# LED-Gauge-Panel.net
KiCad netlist of a schematic drawn in EAGLE
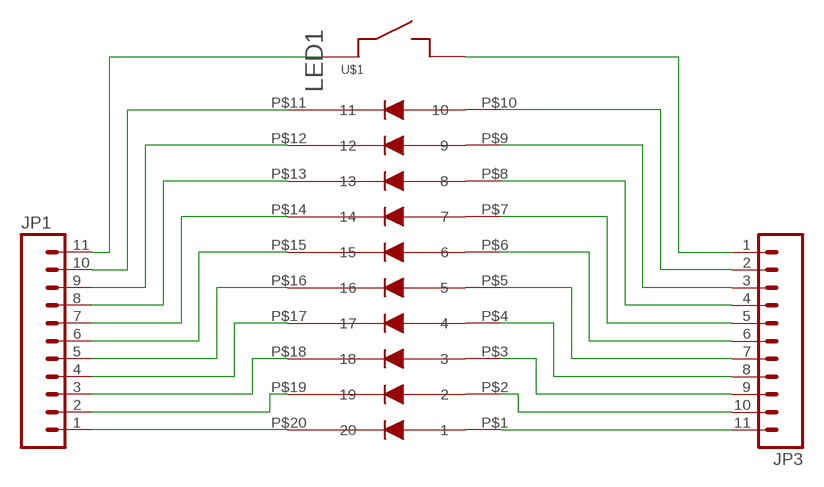
[diagram p0: schematic, sheet 1]

(export (version "E")
  (design (tool "Eeschema 10.0.6"))
  (components
    (comp (ref "JP1")
      (value "M11PTH")
      (footprint "eagle-import:1X11")
      (libsource (lib "eagle-import") (part "M11PTH"))
    )
    (comp (ref "JP3")
      (value "M11PTH")
      (footprint "eagle-import:1X11")
      (libsource (lib "eagle-import") (part "M11PTH"))
    )
    (comp (ref "LED1")
      (value "LED-DC7G3HWA")
      (footprint "eagle-import:LED-10")
      (libsource (lib "eagle-import") (part "LED-DC7G3HWA"))
    )
    (comp (ref "U$1")
      (value "MOMENTARY-SWITCH-EVQ1")
      (footprint "eagle-import:EVQ11")
      (libsource (lib "eagle-import") (part "MOMENTARY-SWITCH-EVQ1"))
    )
  )
  (nets
    (net (code "1") (name "Net-(JP1-Pad11)") (class "Default")
      (node (ref "JP1") (pin "11") (pinfunction "11_11") (pintype "passive"))
      (node (ref "U$1") (pin "P$1") (pinfunction "P$1_P$1") (pintype "bidirectional"))
    )
    (net (code "2") (name "Net-(JP3-Pad1)") (class "Default")
      (node (ref "JP3") (pin "1") (pinfunction "1_1") (pintype "passive"))
      (node (ref "U$1") (pin "P$2") (pinfunction "P$2_P$2") (pintype "bidirectional"))
    )
    (net (code "3") (name "Net-(LED1-1)") (class "Default")
      (node (ref "JP3") (pin "11") (pinfunction "11_11") (pintype "passive"))
      (node (ref "LED1") (pin "P$1") (pinfunction "1_P$1") (pintype "bidirectional"))
    )
    (net (code "4") (name "Net-(LED1-2)") (class "Default")
      (node (ref "JP3") (pin "10") (pinfunction "10_10") (pintype "passive"))
      (node (ref "LED1") (pin "P$2") (pinfunction "2_P$2") (pintype "bidirectional"))
    )
    (net (code "5") (name "Net-(LED1-3)") (class "Default")
      (node (ref "JP3") (pin "9") (pinfunction "9_9") (pintype "passive"))
      (node (ref "LED1") (pin "P$3") (pinfunction "3_P$3") (pintype "bidirectional"))
    )
    (net (code "6") (name "Net-(LED1-4)") (class "Default")
      (node (ref "JP3") (pin "8") (pinfunction "8_8") (pintype "passive"))
      (node (ref "LED1") (pin "P$4") (pinfunction "4_P$4") (pintype "bidirectional"))
    )
    (net (code "7") (name "Net-(LED1-5)") (class "Default")
      (node (ref "JP3") (pin "7") (pinfunction "7_7") (pintype "passive"))
      (node (ref "LED1") (pin "P$5") (pinfunction "5_P$5") (pintype "bidirectional"))
    )
    (net (code "8") (name "Net-(LED1-6)") (class "Default")
      (node (ref "JP3") (pin "6") (pinfunction "6_6") (pintype "passive"))
      (node (ref "LED1") (pin "P$6") (pinfunction "6_P$6") (pintype "bidirectional"))
    )
    (net (code "9") (name "Net-(LED1-7)") (class "Default")
      (node (ref "JP3") (pin "5") (pinfunction "5_5") (pintype "passive"))
      (node (ref "LED1") (pin "P$7") (pinfunction "7_P$7") (pintype "bidirectional"))
    )
    (net (code "10") (name "Net-(LED1-8)") (class "Default")
      (node (ref "JP3") (pin "4") (pinfunction "4_4") (pintype "passive"))
      (node (ref "LED1") (pin "P$8") (pinfunction "8_P$8") (pintype "bidirectional"))
    )
    (net (code "11") (name "Net-(LED1-9)") (class "Default")
      (node (ref "JP3") (pin "3") (pinfunction "3_3") (pintype "passive"))
      (node (ref "LED1") (pin "P$9") (pinfunction "9_P$9") (pintype "bidirectional"))
    )
    (net (code "12") (name "Net-(LED1-10)") (class "Default")
      (node (ref "JP3") (pin "2") (pinfunction "2_2") (pintype "passive"))
      (node (ref "LED1") (pin "P$10") (pinfunction "10_P$10") (pintype "bidirectional"))
    )
    (net (code "13") (name "Net-(LED1-11)") (class "Default")
      (node (ref "JP1") (pin "10") (pinfunction "10_10") (pintype "passive"))
      (node (ref "LED1") (pin "P$11") (pinfunction "11_P$11") (pintype "bidirectional"))
    )
    (net (code "14") (name "Net-(LED1-12)") (class "Default")
      (node (ref "JP1") (pin "9") (pinfunction "9_9") (pintype "passive"))
      (node (ref "LED1") (pin "P$12") (pinfunction "12_P$12") (pintype "bidirectional"))
    )
    (net (code "15") (name "Net-(LED1-13)") (class "Default")
      (node (ref "JP1") (pin "8") (pinfunction "8_8") (pintype "passive"))
      (node (ref "LED1") (pin "P$13") (pinfunction "13_P$13") (pintype "bidirectional"))
    )
    (net (code "16") (name "Net-(LED1-14)") (class "Default")
      (node (ref "JP1") (pin "7") (pinfunction "7_7") (pintype "passive"))
      (node (ref "LED1") (pin "P$14") (pinfunction "14_P$14") (pintype "bidirectional"))
    )
    (net (code "17") (name "Net-(LED1-15)") (class "Default")
      (node (ref "JP1") (pin "6") (pinfunction "6_6") (pintype "passive"))
      (node (ref "LED1") (pin "P$15") (pinfunction "15_P$15") (pintype "bidirectional"))
    )
    (net (code "18") (name "Net-(LED1-16)") (class "Default")
      (node (ref "JP1") (pin "5") (pinfunction "5_5") (pintype "passive"))
      (node (ref "LED1") (pin "P$16") (pinfunction "16_P$16") (pintype "bidirectional"))
    )
    (net (code "19") (name "Net-(LED1-17)") (class "Default")
      (node (ref "JP1") (pin "4") (pinfunction "4_4") (pintype "passive"))
      (node (ref "LED1") (pin "P$17") (pinfunction "17_P$17") (pintype "bidirectional"))
    )
    (net (code "20") (name "Net-(LED1-18)") (class "Default")
      (node (ref "JP1") (pin "3") (pinfunction "3_3") (pintype "passive"))
      (node (ref "LED1") (pin "P$18") (pinfunction "18_P$18") (pintype "bidirectional"))
    )
    (net (code "21") (name "Net-(LED1-19)") (class "Default")
      (node (ref "JP1") (pin "2") (pinfunction "2_2") (pintype "passive"))
      (node (ref "LED1") (pin "P$19") (pinfunction "19_P$19") (pintype "bidirectional"))
    )
    (net (code "22") (name "Net-(LED1-20)") (class "Default")
      (node (ref "JP1") (pin "1") (pinfunction "1_1") (pintype "passive"))
      (node (ref "LED1") (pin "P$20") (pinfunction "20_P$20") (pintype "bidirectional"))
    )
  )
)
